# board.net
KiCad netlist of a schematic drawn in EAGLE
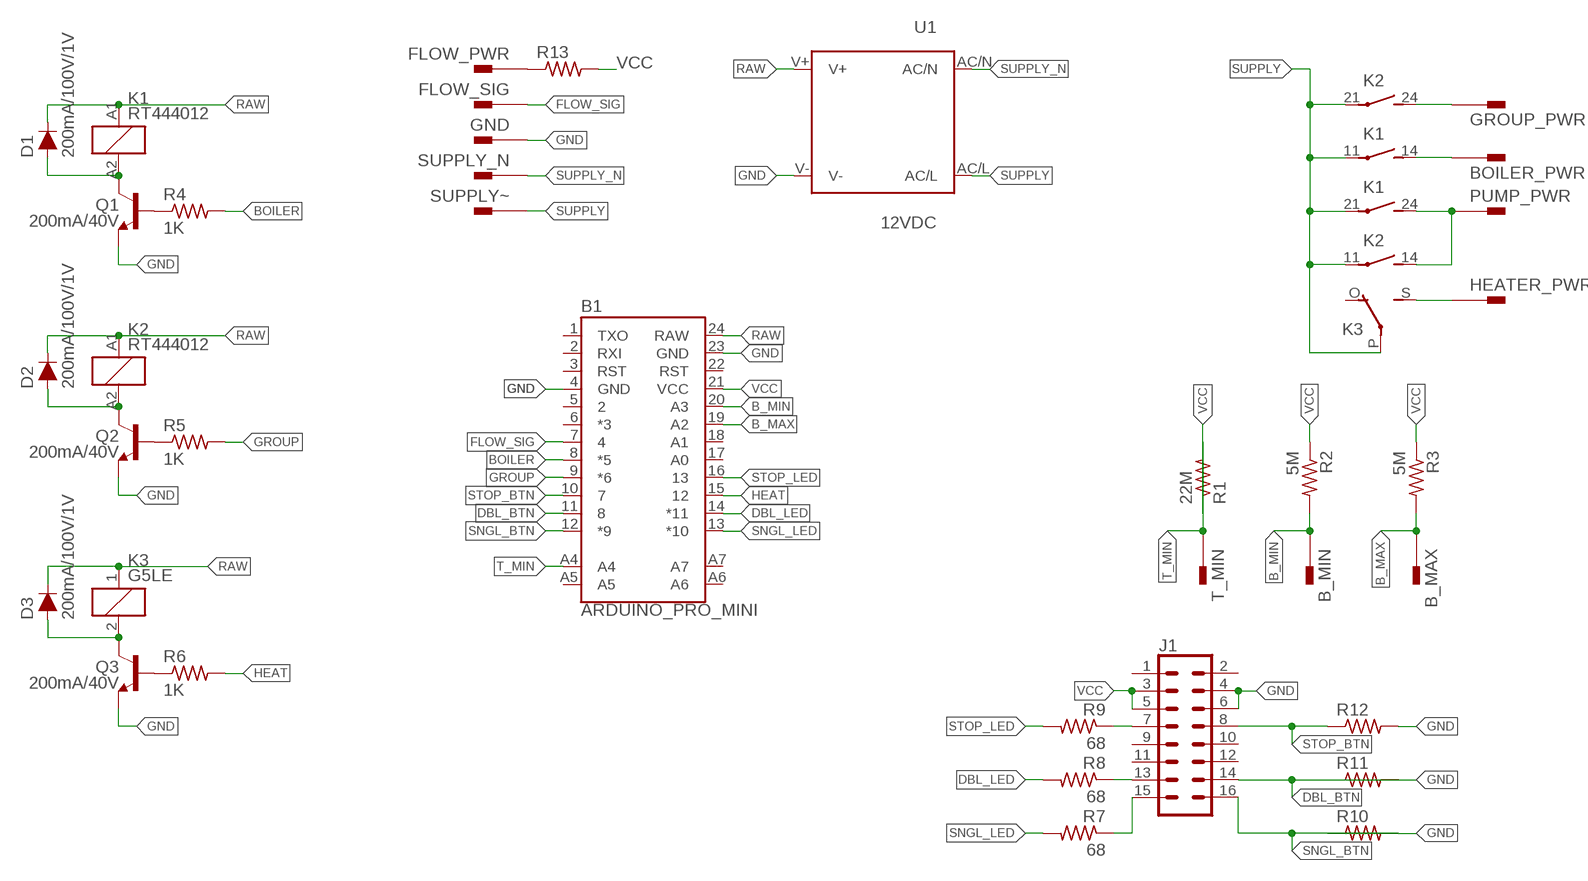
[diagram p0: schematic, sheet 1]

(export (version "E")
  (design (tool "Eeschema 10.0.6"))
  (components
    (comp (ref "B1")
      (value "ARDUINO_PRO_MINI")
      (footprint "eagle-import:ARDUINO_PRO_MINI")
      (libsource (lib "eagle-import") (part "ARDUINO_PRO_MINI"))
    )
    (comp (ref "BOILER_PWR")
      (value "PIN2F061.040")
      (footprint "eagle-import:F061.040")
      (libsource (lib "eagle-import") (part "PIN2F061.040"))
    )
    (comp (ref "B_MAX")
      (value "PIN2F061.040")
      (footprint "eagle-import:F061.040")
      (libsource (lib "eagle-import") (part "PIN2F061.040"))
    )
    (comp (ref "B_MIN")
      (value "PIN2F061.040")
      (footprint "eagle-import:F061.040")
      (libsource (lib "eagle-import") (part "PIN2F061.040"))
    )
    (comp (ref "D1")
      (value "200mA/100V/1V")
      (footprint "eagle-import:DIODE-1N4148")
      (libsource (lib "eagle-import") (part "DIODE-1N4148"))
    )
    (comp (ref "D2")
      (value "200mA/100V/1V")
      (footprint "eagle-import:DIODE-1N4148")
      (libsource (lib "eagle-import") (part "DIODE-1N4148"))
    )
    (comp (ref "D3")
      (value "200mA/100V/1V")
      (footprint "eagle-import:DIODE-1N4148")
      (libsource (lib "eagle-import") (part "DIODE-1N4148"))
    )
    (comp (ref "FLOW_PWR")
      (value "PIN2F061.040")
      (footprint "eagle-import:F061.040")
      (libsource (lib "eagle-import") (part "PIN2F061.040"))
    )
    (comp (ref "FLOW_SIG")
      (value "PIN2F061.040")
      (footprint "eagle-import:F061.040")
      (libsource (lib "eagle-import") (part "PIN2F061.040"))
    )
    (comp (ref "GND")
      (value "PIN2F061.040")
      (footprint "eagle-import:F061.040")
      (libsource (lib "eagle-import") (part "PIN2F061.040"))
    )
    (comp (ref "GROUP_PWR")
      (value "PIN2F061.040")
      (footprint "eagle-import:F061.040")
      (libsource (lib "eagle-import") (part "PIN2F061.040"))
    )
    (comp (ref "HEATER_PWR")
      (value "PIN2F061.040")
      (footprint "eagle-import:F061.040")
      (libsource (lib "eagle-import") (part "PIN2F061.040"))
    )
    (comp (ref "J1")
      (value "CONN_08X2")
      (footprint "eagle-import:2X8")
      (libsource (lib "eagle-import") (part "CONN_08X2"))
    )
    (comp (ref "K1")
      (value "RT444012")
      (footprint "eagle-import:RT2N_O")
      (libsource (lib "eagle-import") (part "RT44?4012"))
    )
    (comp (ref "K2")
      (value "RT444012")
      (footprint "eagle-import:RT2N_O")
      (libsource (lib "eagle-import") (part "RT44?4012"))
    )
    (comp (ref "K3")
      (value "G5LE")
      (footprint "eagle-import:G5LE")
      (libsource (lib "eagle-import") (part "G5LE"))
    )
    (comp (ref "PUMP_PWR")
      (value "PIN2F061.040")
      (footprint "eagle-import:F061.040")
      (libsource (lib "eagle-import") (part "PIN2F061.040"))
    )
    (comp (ref "Q1")
      (value "200mA/40V")
      (footprint "eagle-import:TO-92")
      (libsource (lib "eagle-import") (part "TRANS_NPN-2N3904"))
    )
    (comp (ref "Q2")
      (value "200mA/40V")
      (footprint "eagle-import:TO-92")
      (libsource (lib "eagle-import") (part "TRANS_NPN-2N3904"))
    )
    (comp (ref "Q3")
      (value "200mA/40V")
      (footprint "eagle-import:TO-92")
      (libsource (lib "eagle-import") (part "TRANS_NPN-2N3904"))
    )
    (comp (ref "R1")
      (value "22M")
      (footprint "eagle-import:0207_7")
      (libsource (lib "eagle-import") (part "R-US_0207/7"))
    )
    (comp (ref "R2")
      (value "5M")
      (footprint "eagle-import:0207_7")
      (libsource (lib "eagle-import") (part "R-US_0207/7"))
    )
    (comp (ref "R3")
      (value "5M")
      (footprint "eagle-import:0207_7")
      (libsource (lib "eagle-import") (part "R-US_0207/7"))
    )
    (comp (ref "R4")
      (value "1K")
      (footprint "eagle-import:0207_7")
      (libsource (lib "eagle-import") (part "R-US_0207/7"))
    )
    (comp (ref "R5")
      (value "1K")
      (footprint "eagle-import:0207_7")
      (libsource (lib "eagle-import") (part "R-US_0207/7"))
    )
    (comp (ref "R6")
      (value "1K")
      (footprint "eagle-import:0207_7")
      (libsource (lib "eagle-import") (part "R-US_0207/7"))
    )
    (comp (ref "R7")
      (value "68")
      (footprint "eagle-import:0207_7")
      (libsource (lib "eagle-import") (part "R-US_0207/7"))
    )
    (comp (ref "R8")
      (value "68")
      (footprint "eagle-import:0207_7")
      (libsource (lib "eagle-import") (part "R-US_0207/7"))
    )
    (comp (ref "R9")
      (value "68")
      (footprint "eagle-import:0207_7")
      (libsource (lib "eagle-import") (part "R-US_0207/7"))
    )
    (comp (ref "R10")
      (value "R-US_0207/7")
      (footprint "eagle-import:0207_7")
      (libsource (lib "eagle-import") (part "R-US_0207/7"))
    )
    (comp (ref "R11")
      (value "R-US_0207/7")
      (footprint "eagle-import:0207_7")
      (libsource (lib "eagle-import") (part "R-US_0207/7"))
    )
    (comp (ref "R12")
      (value "R-US_0207/7")
      (footprint "eagle-import:0207_7")
      (libsource (lib "eagle-import") (part "R-US_0207/7"))
    )
    (comp (ref "R13")
      (value "R-US_0207/7")
      (footprint "eagle-import:0207_7")
      (libsource (lib "eagle-import") (part "R-US_0207/7"))
    )
    (comp (ref "SUPPLY_N")
      (value "PIN2F061.040")
      (footprint "eagle-import:F061.040")
      (libsource (lib "eagle-import") (part "PIN2F061.040"))
    )
    (comp (ref "SUPPLY~")
      (value "PIN2F061.040")
      (footprint "eagle-import:F061.040")
      (libsource (lib "eagle-import") (part "PIN2F061.040"))
    )
    (comp (ref "T_MIN")
      (value "PIN2F061.040")
      (footprint "eagle-import:F061.040")
      (libsource (lib "eagle-import") (part "PIN2F061.040"))
    )
    (comp (ref "U1")
      (value "12VDC")
      (footprint "eagle-import:IRM_05_10")
      (libsource (lib "eagle-import") (part "IRM_05/10"))
    )
  )
  (nets
    (net (code "1") (name "BOILER") (class "Default")
      (node (ref "B1") (pin "8") (pinfunction "*5_8") (pintype "bidirectional"))
      (node (ref "R4") (pin "2") (pinfunction "2_2") (pintype "passive"))
    )
    (net (code "2") (name "B_MAX") (class "Default")
      (node (ref "B1") (pin "19") (pinfunction "A2_19") (pintype "bidirectional"))
      (node (ref "B_MAX") (pin "A1") (pinfunction "1_A1") (pintype "passive"))
      (node (ref "B_MAX") (pin "A2") (pinfunction "1_A2") (pintype "passive"))
      (node (ref "R3") (pin "2") (pinfunction "2_2") (pintype "passive"))
    )
    (net (code "3") (name "B_MIN") (class "Default")
      (node (ref "B1") (pin "20") (pinfunction "A3_20") (pintype "bidirectional"))
      (node (ref "B_MIN") (pin "A1") (pinfunction "1_A1") (pintype "passive"))
      (node (ref "B_MIN") (pin "A2") (pinfunction "1_A2") (pintype "passive"))
      (node (ref "R2") (pin "2") (pinfunction "2_2") (pintype "passive"))
    )
    (net (code "4") (name "DBL_BTN") (class "Default")
      (node (ref "B1") (pin "11") (pinfunction "8_11") (pintype "bidirectional"))
      (node (ref "J1") (pin "14") (pinfunction "14_14") (pintype "passive"))
      (node (ref "R11") (pin "2") (pinfunction "2_2") (pintype "passive"))
    )
    (net (code "5") (name "DBL_LED") (class "Default")
      (node (ref "B1") (pin "14") (pinfunction "*11_14") (pintype "bidirectional"))
      (node (ref "R8") (pin "2") (pinfunction "2_2") (pintype "passive"))
    )
    (net (code "6") (name "FLOW_SIG") (class "Default")
      (node (ref "B1") (pin "7") (pinfunction "4_7") (pintype "bidirectional"))
      (node (ref "FLOW_SIG") (pin "A1") (pinfunction "1_A1") (pintype "passive"))
      (node (ref "FLOW_SIG") (pin "A2") (pinfunction "1_A2") (pintype "passive"))
    )
    (net (code "7") (name "GND") (class "Default")
      (node (ref "B1") (pin "23") (pinfunction "GND_23") (pintype "power_in"))
      (node (ref "B1") (pin "4") (pinfunction "GND_4") (pintype "power_in"))
      (node (ref "GND") (pin "A1") (pinfunction "1_A1") (pintype "passive"))
      (node (ref "GND") (pin "A2") (pinfunction "1_A2") (pintype "passive"))
      (node (ref "J1") (pin "4") (pinfunction "4_4") (pintype "passive"))
      (node (ref "J1") (pin "6") (pinfunction "6_6") (pintype "passive"))
      (node (ref "Q1") (pin "1") (pinfunction "E_1") (pintype "passive"))
      (node (ref "Q2") (pin "1") (pinfunction "E_1") (pintype "passive"))
      (node (ref "Q3") (pin "1") (pinfunction "E_1") (pintype "passive"))
      (node (ref "R10") (pin "1") (pinfunction "1_1") (pintype "passive"))
      (node (ref "R11") (pin "1") (pinfunction "1_1") (pintype "passive"))
      (node (ref "R12") (pin "2") (pinfunction "2_2") (pintype "passive"))
      (node (ref "U1") (pin "V-") (pinfunction "V-_V-") (pintype "output"))
    )
    (net (code "8") (name "GROUP") (class "Default")
      (node (ref "B1") (pin "9") (pinfunction "*6_9") (pintype "bidirectional"))
      (node (ref "R5") (pin "2") (pinfunction "2_2") (pintype "passive"))
    )
    (net (code "9") (name "HEAT") (class "Default")
      (node (ref "B1") (pin "15") (pinfunction "12_15") (pintype "bidirectional"))
      (node (ref "R6") (pin "2") (pinfunction "2_2") (pintype "passive"))
    )
    (net (code "10") (name "Net-(FLOW_PWR-1-PadA1)") (class "Default")
      (node (ref "FLOW_PWR") (pin "A1") (pinfunction "1_A1") (pintype "passive"))
      (node (ref "FLOW_PWR") (pin "A2") (pinfunction "1_A2") (pintype "passive"))
      (node (ref "R13") (pin "1") (pinfunction "1_1") (pintype "passive"))
    )
    (net (code "11") (name "Net-(HEATER_PWR-1-PadA1)") (class "Default")
      (node (ref "HEATER_PWR") (pin "A1") (pinfunction "1_A1") (pintype "passive"))
      (node (ref "HEATER_PWR") (pin "A2") (pinfunction "1_A2") (pintype "passive"))
      (node (ref "K3") (pin "S") (pinfunction "S_S") (pintype "passive"))
    )
    (net (code "12") (name "Net-(J1-Pad7)") (class "Default")
      (node (ref "J1") (pin "7") (pinfunction "7_7") (pintype "passive"))
      (node (ref "R9") (pin "1") (pinfunction "1_1") (pintype "passive"))
    )
    (net (code "13") (name "Net-(J1-Pad13)") (class "Default")
      (node (ref "J1") (pin "13") (pinfunction "13_13") (pintype "passive"))
      (node (ref "R8") (pin "1") (pinfunction "1_1") (pintype "passive"))
    )
    (net (code "14") (name "Net-(J1-Pad15)") (class "Default")
      (node (ref "J1") (pin "15") (pinfunction "15_15") (pintype "passive"))
      (node (ref "R7") (pin "1") (pinfunction "1_1") (pintype "passive"))
    )
    (net (code "15") (name "Net-(K1A-2)") (class "Default")
      (node (ref "D1") (pin "A") (pinfunction "A_A") (pintype "passive"))
      (node (ref "K1") (pin "A2") (pinfunction "2_A2") (pintype "passive"))
      (node (ref "Q1") (pin "3") (pinfunction "C_3") (pintype "passive"))
    )
    (net (code "16") (name "Net-(K1B-S)") (class "Default")
      (node (ref "BOILER_PWR") (pin "A1") (pinfunction "1_A1") (pintype "passive"))
      (node (ref "BOILER_PWR") (pin "A2") (pinfunction "1_A2") (pintype "passive"))
      (node (ref "K1") (pin "14") (pinfunction "S_14") (pintype "passive"))
    )
    (net (code "17") (name "Net-(K1C-S)") (class "Default")
      (node (ref "K1") (pin "24") (pinfunction "S_24") (pintype "passive"))
      (node (ref "K2") (pin "14") (pinfunction "S_14") (pintype "passive"))
      (node (ref "PUMP_PWR") (pin "A1") (pinfunction "1_A1") (pintype "passive"))
      (node (ref "PUMP_PWR") (pin "A2") (pinfunction "1_A2") (pintype "passive"))
    )
    (net (code "18") (name "Net-(K2A-2)") (class "Default")
      (node (ref "D2") (pin "A") (pinfunction "A_A") (pintype "passive"))
      (node (ref "K2") (pin "A2") (pinfunction "2_A2") (pintype "passive"))
      (node (ref "Q2") (pin "3") (pinfunction "C_3") (pintype "passive"))
    )
    (net (code "19") (name "Net-(K2C-S)") (class "Default")
      (node (ref "GROUP_PWR") (pin "A1") (pinfunction "1_A1") (pintype "passive"))
      (node (ref "GROUP_PWR") (pin "A2") (pinfunction "1_A2") (pintype "passive"))
      (node (ref "K2") (pin "24") (pinfunction "S_24") (pintype "passive"))
    )
    (net (code "20") (name "Net-(Q1-B)") (class "Default")
      (node (ref "Q1") (pin "2") (pinfunction "B_2") (pintype "passive"))
      (node (ref "R4") (pin "1") (pinfunction "1_1") (pintype "passive"))
    )
    (net (code "21") (name "Net-(Q2-B)") (class "Default")
      (node (ref "Q2") (pin "2") (pinfunction "B_2") (pintype "passive"))
      (node (ref "R5") (pin "1") (pinfunction "1_1") (pintype "passive"))
    )
    (net (code "22") (name "Net-(Q3-B)") (class "Default")
      (node (ref "Q3") (pin "2") (pinfunction "B_2") (pintype "passive"))
      (node (ref "R6") (pin "1") (pinfunction "1_1") (pintype "passive"))
    )
    (net (code "23") (name "Net-(Q3-C)") (class "Default")
      (node (ref "D3") (pin "A") (pinfunction "A_A") (pintype "passive"))
      (node (ref "K3") (pin "2") (pinfunction "2_2") (pintype "passive"))
      (node (ref "Q3") (pin "3") (pinfunction "C_3") (pintype "passive"))
    )
    (net (code "24") (name "RAW") (class "Default")
      (node (ref "B1") (pin "24") (pinfunction "RAW_24") (pintype "power_in"))
      (node (ref "D1") (pin "C") (pinfunction "C_C") (pintype "passive"))
      (node (ref "D2") (pin "C") (pinfunction "C_C") (pintype "passive"))
      (node (ref "D3") (pin "C") (pinfunction "C_C") (pintype "passive"))
      (node (ref "K1") (pin "A1") (pinfunction "1_A1") (pintype "passive"))
      (node (ref "K2") (pin "A1") (pinfunction "1_A1") (pintype "passive"))
      (node (ref "K3") (pin "1") (pinfunction "1_1") (pintype "passive"))
      (node (ref "U1") (pin "V+") (pinfunction "V+_V+") (pintype "output"))
    )
    (net (code "25") (name "SNGL_BTN") (class "Default")
      (node (ref "B1") (pin "12") (pinfunction "*9_12") (pintype "bidirectional"))
      (node (ref "J1") (pin "16") (pinfunction "16_16") (pintype "passive"))
      (node (ref "R10") (pin "2") (pinfunction "2_2") (pintype "passive"))
    )
    (net (code "26") (name "SNGL_LED") (class "Default")
      (node (ref "B1") (pin "13") (pinfunction "*10_13") (pintype "bidirectional"))
      (node (ref "R7") (pin "2") (pinfunction "2_2") (pintype "passive"))
    )
    (net (code "27") (name "STOP_BTN") (class "Default")
      (node (ref "B1") (pin "10") (pinfunction "7_10") (pintype "bidirectional"))
      (node (ref "J1") (pin "8") (pinfunction "8_8") (pintype "passive"))
      (node (ref "R12") (pin "1") (pinfunction "1_1") (pintype "passive"))
    )
    (net (code "28") (name "STOP_LED") (class "Default")
      (node (ref "B1") (pin "16") (pinfunction "13_16") (pintype "bidirectional"))
      (node (ref "R9") (pin "2") (pinfunction "2_2") (pintype "passive"))
    )
    (net (code "29") (name "SUPPLY") (class "Default")
      (node (ref "K1") (pin "11") (pinfunction "P_11") (pintype "passive"))
      (node (ref "K1") (pin "21") (pinfunction "P_21") (pintype "passive"))
      (node (ref "K2") (pin "11") (pinfunction "P_11") (pintype "passive"))
      (node (ref "K2") (pin "21") (pinfunction "P_21") (pintype "passive"))
      (node (ref "K3") (pin "P") (pinfunction "P_P") (pintype "passive"))
      (node (ref "SUPPLY~") (pin "A1") (pinfunction "1_A1") (pintype "passive"))
      (node (ref "SUPPLY~") (pin "A2") (pinfunction "1_A2") (pintype "passive"))
      (node (ref "U1") (pin "AC/L") (pinfunction "AC/L_AC/L") (pintype "input"))
    )
    (net (code "30") (name "SUPPLY_N") (class "Default")
      (node (ref "SUPPLY_N") (pin "A1") (pinfunction "1_A1") (pintype "passive"))
      (node (ref "SUPPLY_N") (pin "A2") (pinfunction "1_A2") (pintype "passive"))
      (node (ref "U1") (pin "AC/N") (pinfunction "AC/N_AC/N") (pintype "input"))
    )
    (net (code "31") (name "T_MIN") (class "Default")
      (node (ref "B1") (pin "A4") (pinfunction "A4_A4") (pintype "bidirectional"))
      (node (ref "R1") (pin "2") (pinfunction "2_2") (pintype "passive"))
      (node (ref "T_MIN") (pin "A1") (pinfunction "1_A1") (pintype "passive"))
      (node (ref "T_MIN") (pin "A2") (pinfunction "1_A2") (pintype "passive"))
    )
    (net (code "32") (name "VCC") (class "Default")
      (node (ref "B1") (pin "21") (pinfunction "VCC_21") (pintype "power_in"))
      (node (ref "J1") (pin "3") (pinfunction "3_3") (pintype "passive"))
      (node (ref "J1") (pin "5") (pinfunction "5_5") (pintype "passive"))
      (node (ref "R1") (pin "1") (pinfunction "1_1") (pintype "passive"))
      (node (ref "R13") (pin "2") (pinfunction "2_2") (pintype "passive"))
      (node (ref "R2") (pin "1") (pinfunction "1_1") (pintype "passive"))
      (node (ref "R3") (pin "1") (pinfunction "1_1") (pintype "passive"))
    )
    (net (code "33") (name "unconnected-(B1-*3-Pad6)") (class "Default")
      (node (ref "B1") (pin "6") (pinfunction "*3_6") (pintype "bidirectional"))
    )
    (net (code "34") (name "unconnected-(B1-2-Pad5)") (class "Default")
      (node (ref "B1") (pin "5") (pinfunction "2_5") (pintype "bidirectional"))
    )
    (net (code "35") (name "unconnected-(B1-A0-Pad17)") (class "Default")
      (node (ref "B1") (pin "17") (pinfunction "A0_17") (pintype "bidirectional"))
    )
    (net (code "36") (name "unconnected-(B1-A1-Pad18)") (class "Default")
      (node (ref "B1") (pin "18") (pinfunction "A1_18") (pintype "bidirectional"))
    )
    (net (code "37") (name "unconnected-(B1-PadA5)") (class "Default")
      (node (ref "B1") (pin "A5") (pinfunction "A5_A5") (pintype "bidirectional"))
    )
    (net (code "38") (name "unconnected-(B1-PadA6)") (class "Default")
      (node (ref "B1") (pin "A6") (pinfunction "A6_A6") (pintype "bidirectional"))
    )
    (net (code "39") (name "unconnected-(B1-PadA7)") (class "Default")
      (node (ref "B1") (pin "A7") (pinfunction "A7_A7") (pintype "bidirectional"))
    )
    (net (code "40") (name "unconnected-(B1-RST-Pad3)") (class "Default")
      (node (ref "B1") (pin "3") (pinfunction "RST_3") (pintype "bidirectional"))
    )
    (net (code "41") (name "unconnected-(B1-RST-Pad22)") (class "Default")
      (node (ref "B1") (pin "22") (pinfunction "RST_22") (pintype "bidirectional"))
    )
    (net (code "42") (name "unconnected-(B1-RXI-Pad2)") (class "Default")
      (node (ref "B1") (pin "2") (pinfunction "RXI_2") (pintype "bidirectional"))
    )
    (net (code "43") (name "unconnected-(B1-TXO-Pad1)") (class "Default")
      (node (ref "B1") (pin "1") (pinfunction "TXO_1") (pintype "bidirectional"))
    )
    (net (code "44") (name "unconnected-(J1-Pad1)") (class "Default")
      (node (ref "J1") (pin "1") (pinfunction "1_1") (pintype "passive"))
    )
    (net (code "45") (name "unconnected-(J1-Pad2)") (class "Default")
      (node (ref "J1") (pin "2") (pinfunction "2_2") (pintype "passive"))
    )
    (net (code "46") (name "unconnected-(J1-Pad9)") (class "Default")
      (node (ref "J1") (pin "9") (pinfunction "9_9") (pintype "passive"))
    )
    (net (code "47") (name "unconnected-(J1-Pad10)") (class "Default")
      (node (ref "J1") (pin "10") (pinfunction "10_10") (pintype "passive"))
    )
    (net (code "48") (name "unconnected-(J1-Pad11)") (class "Default")
      (node (ref "J1") (pin "11") (pinfunction "11_11") (pintype "passive"))
    )
    (net (code "49") (name "unconnected-(J1-Pad12)") (class "Default")
      (node (ref "J1") (pin "12") (pinfunction "12_12") (pintype "passive"))
    )
    (net (code "50") (name "unconnected-(K3-PadO)") (class "Default")
      (node (ref "K3") (pin "O") (pinfunction "O_O") (pintype "passive"))
    )
  )
)
